# ideal_diode_ch0.net
KiCad netlist of a schematic drawn in Altium Designer
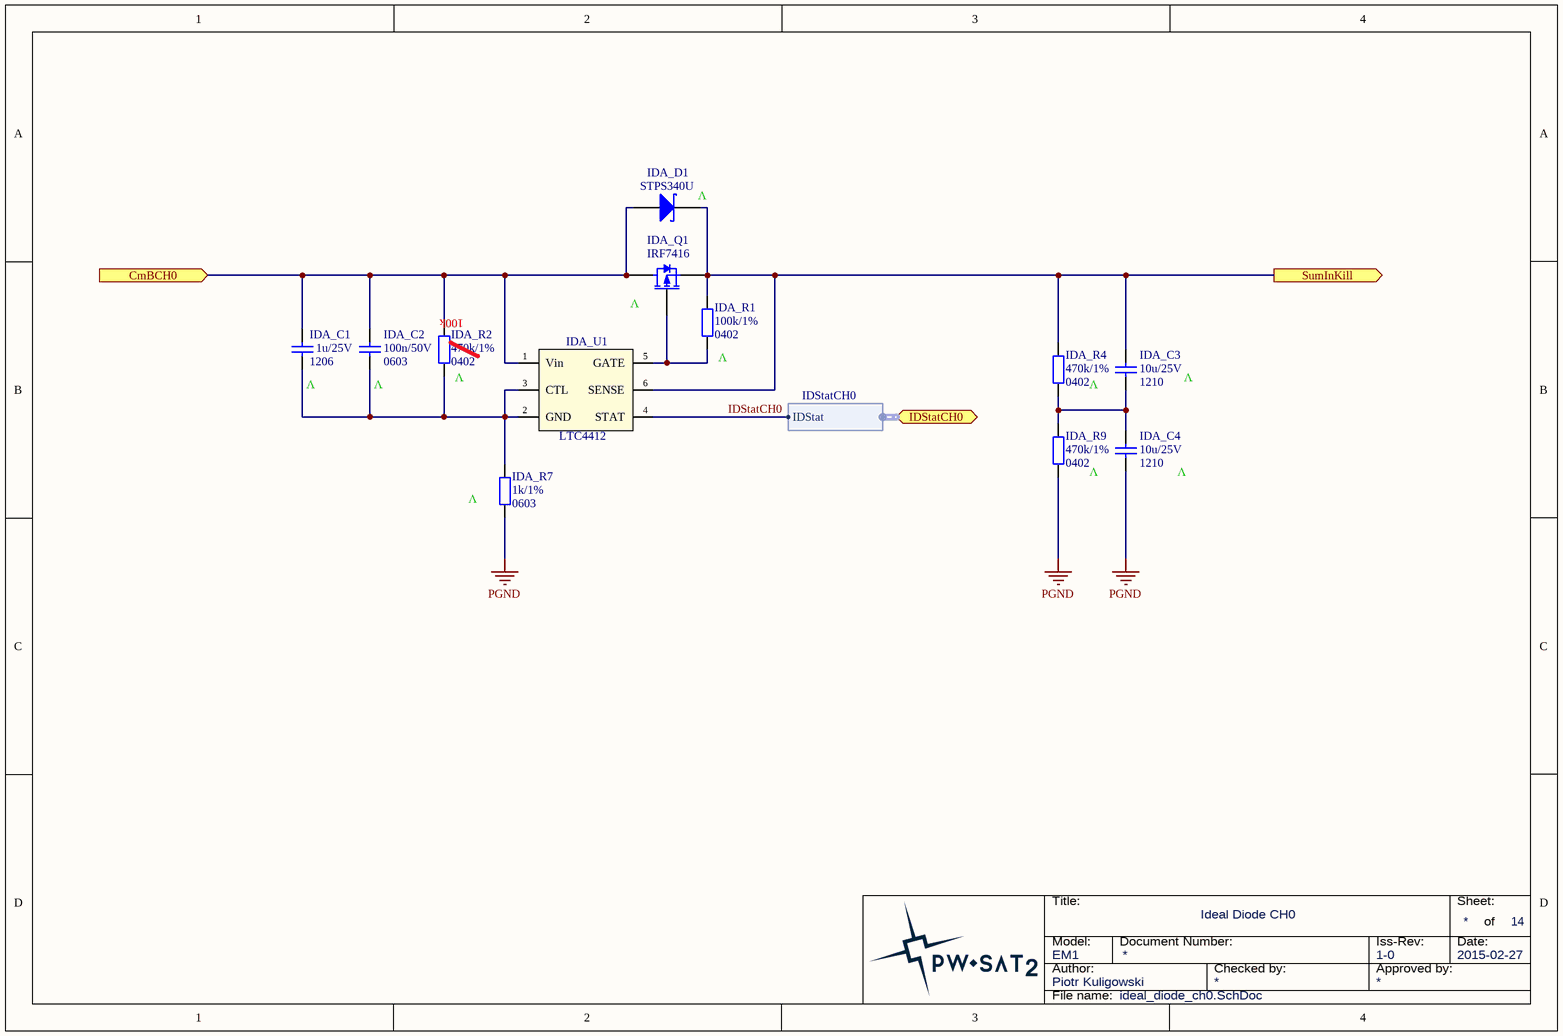
[diagram p0: ideal_diode_ch0.SchDoc]

(export (version "E")
  (design (tool "Eeschema 10.0.6"))
  (components
    (comp (ref "IDA_C1")
      (value "1u/25V")
      (footprint "SMD_Capacitor_1206")
      (description "Ceramic Cap Kemet COTS 1u/25V X7R 1206")
      (fields
        (field (name "MANUFACTURERPARTNUMBER") "C1206T105K3RALTU")
        (field (name "MANUFACTURER") "Kemet")
        (field (name "PACKAGE") "1206")
      )
      (libsource (lib "capacitors") (part "Cer_C1206T105K3RALTU"))
    )
    (comp (ref "IDA_C2")
      (value "100n/50V")
      (footprint "SMD_Capacitor_0603")
      (description "Ceramic Cap Murata Automotive 100n/50V X7R 0603")
      (fields
        (field (name "MANUFACTURER") "Murata")
        (field (name "MANUFACTURERPARTNUMBER") "GCJ188R71H104KA12D")
        (field (name "PACKAGE") "0603")
      )
      (libsource (lib "capacitors") (part "Cer_GCJ188R71H104KA12D"))
    )
    (comp (ref "IDA_C3")
      (value "10u/25V")
      (footprint "SMD_Capacitor_1210")
      (description "Ceramic Cap Murata Automotive 10u/25V X7R 1210")
      (fields
        (field (name "MANUFACTURER") "Murata")
        (field (name "MANUFACTURERPARTNUMBER") "GCJ32ER71E106KA12L")
        (field (name "PACKAGE") "1210")
      )
      (libsource (lib "capacitors") (part "Cer_GCJ32ER71E106KA12L"))
    )
    (comp (ref "IDA_C4")
      (value "10u/25V")
      (footprint "SMD_Capacitor_1210")
      (description "Ceramic Cap Murata Automotive 10u/25V X7R 1210")
      (fields
        (field (name "MANUFACTURER") "Murata")
        (field (name "MANUFACTURERPARTNUMBER") "GCJ32ER71E106KA12L")
        (field (name "PACKAGE") "1210")
      )
      (libsource (lib "capacitors") (part "Cer_GCJ32ER71E106KA12L"))
    )
    (comp (ref "IDA_D1")
      (value "STPS340U")
      (footprint "DO-214AA")
      (description "3A/40V Power Schottky Rectifier.")
      (fields (field (name "MANUFACTURER") "STMicroelectronics"))
      (libsource (lib "diodes") (part "STPS340x"))
    )
    (comp (ref "IDA_Q1")
      (value "IRF7416")
      (footprint "SOIC-8-N_SSSGDDDD")
      (description "10A/30V HEXFET Power P-MOSFET.")
      (fields (field (name "MANUFACTURER") "International Rectifier"))
      (libsource (lib "transistors") (part "IRF7416"))
    )
    (comp (ref "IDA_R1")
      (value "100k/1%")
      (footprint "SMD_Resistor_0402")
      (description "100k/1% Vishay CRCW 0402 Resistor. 63mW, 100ppm, 50V.")
      (fields (field (name "MANUFACTURER") "Vishay") (field (name "PACKAGE") "0402"))
      (libsource (lib "resistors") (part "CRCW0402100KFKxxxx"))
    )
    (comp (ref "IDA_R2")
      (value "470k/1%")
      (footprint "SMD_Resistor_0402")
      (description "470k/1% Vishay CRCW 0402 Resistor. 63mW, 100ppm, 50V.")
      (fields
        (field (name "MANUFACTURER") "Vishay")
        (field (name "MANUFACTURERPARTNUMBER") "CRCW0402470KFKxxxx")
        (field (name "PACKAGE") "0402")
      )
      (libsource (lib "resistors") (part "CRCW0402470KFKxxxx"))
    )
    (comp (ref "IDA_R4")
      (value "470k/1%")
      (footprint "SMD_Resistor_0402")
      (description "470k/1% Vishay CRCW 0402 Resistor. 63mW, 100ppm, 50V.")
      (fields
        (field (name "MANUFACTURER") "Vishay")
        (field (name "MANUFACTURERPARTNUMBER") "CRCW0402470KFKxxxx")
        (field (name "PACKAGE") "0402")
      )
      (libsource (lib "resistors") (part "CRCW0402470KFKxxxx"))
    )
    (comp (ref "IDA_R7")
      (value "1k/1%")
      (footprint "SMD_Resistor_0603")
      (description "1k/1% Vishay CRCW 0603 Resistor. 100mW, 100ppm, 75V.")
      (fields
        (field (name "MANUFACTURER") "Vishay")
        (field (name "MANUFACTURERPARTNUMBER") "CRCW06031K00FKxxxx")
        (field (name "PACKAGE") "0603")
      )
      (libsource (lib "resistors") (part "CRCW06031K00FKxxxx"))
    )
    (comp (ref "IDA_R9")
      (value "470k/1%")
      (footprint "SMD_Resistor_0402")
      (description "470k/1% Vishay CRCW 0402 Resistor. 63mW, 100ppm, 50V.")
      (fields
        (field (name "MANUFACTURER") "Vishay")
        (field (name "MANUFACTURERPARTNUMBER") "CRCW0402470KFKxxxx")
        (field (name "PACKAGE") "0402")
      )
      (libsource (lib "resistors") (part "CRCW0402470KFKxxxx"))
    )
    (comp (ref "IDA_U1")
      (value "LTC4412")
      (footprint "SOT23-6")
      (description "Ideal Diode, Low Loss PowerPath Controller.")
      (fields (field (name "MANUFACTURER") "Linear Technology"))
      (libsource (lib "microcircuits") (part "LTC4412"))
    )
  )
  (nets
    (net (code "1") (name "/CmBCH0") (class "Default")
      (node (ref "IDA_C1") (pin "1") (pinfunction "1_1") (pintype "passive"))
      (node (ref "IDA_C2") (pin "1") (pinfunction "1_1") (pintype "passive"))
      (node (ref "IDA_D1") (pin "A") (pinfunction "A_A") (pintype "passive"))
      (node (ref "IDA_Q1") (pin "D") (pinfunction "D_D") (pintype "passive"))
      (node (ref "IDA_R2") (pin "1") (pinfunction "1_1") (pintype "passive"))
      (node (ref "IDA_U1") (pin "1") (pinfunction "Vin_1") (pintype "passive"))
    )
    (net (code "2") (name "/IDStatCH0") (class "Default")
      (node (ref "IDA_U1") (pin "4") (pinfunction "STAT_4") (pintype "passive"))
    )
    (net (code "3") (name "/SumInKill") (class "Default")
      (node (ref "IDA_C3") (pin "1") (pinfunction "1_1") (pintype "passive"))
      (node (ref "IDA_D1") (pin "K") (pinfunction "K_K") (pintype "passive"))
      (node (ref "IDA_Q1") (pin "S") (pinfunction "S_S") (pintype "passive"))
      (node (ref "IDA_R1") (pin "1") (pinfunction "1_1") (pintype "passive"))
      (node (ref "IDA_R4") (pin "1") (pinfunction "1_1") (pintype "passive"))
      (node (ref "IDA_U1") (pin "6") (pinfunction "SENSE_6") (pintype "passive"))
    )
    (net (code "5") (name "Net-(IDA_C3-Pad2)") (class "Default")
      (node (ref "IDA_C3") (pin "2") (pinfunction "2_2") (pintype "passive"))
      (node (ref "IDA_C4") (pin "1") (pinfunction "1_1") (pintype "passive"))
      (node (ref "IDA_R4") (pin "2") (pinfunction "2_2") (pintype "passive"))
      (node (ref "IDA_R9") (pin "1") (pinfunction "1_1") (pintype "passive"))
    )
    (net (code "6") (name "Net-(IDA_U1-CTL)") (class "Default")
      (node (ref "IDA_C1") (pin "2") (pinfunction "2_2") (pintype "passive"))
      (node (ref "IDA_C2") (pin "2") (pinfunction "2_2") (pintype "passive"))
      (node (ref "IDA_R2") (pin "2") (pinfunction "2_2") (pintype "passive"))
      (node (ref "IDA_R7") (pin "1") (pinfunction "1_1") (pintype "passive"))
      (node (ref "IDA_U1") (pin "2") (pinfunction "GND_2") (pintype "passive"))
      (node (ref "IDA_U1") (pin "3") (pinfunction "CTL_3") (pintype "passive"))
    )
    (net (code "7") (name "Net-(IDA_U1-GATE)") (class "Default")
      (node (ref "IDA_Q1") (pin "G") (pinfunction "G_G") (pintype "passive"))
      (node (ref "IDA_R1") (pin "2") (pinfunction "2_2") (pintype "passive"))
      (node (ref "IDA_U1") (pin "5") (pinfunction "GATE_5") (pintype "passive"))
    )
    (net (code "8") (name "PGND") (class "Default")
      (node (ref "IDA_C4") (pin "2") (pinfunction "2_2") (pintype "passive"))
      (node (ref "IDA_R7") (pin "2") (pinfunction "2_2") (pintype "passive"))
      (node (ref "IDA_R9") (pin "2") (pinfunction "2_2") (pintype "passive"))
    )
  )
)
